# SHC_USB_HUB.net
KiCad netlist of a schematic drawn in EasyEDA
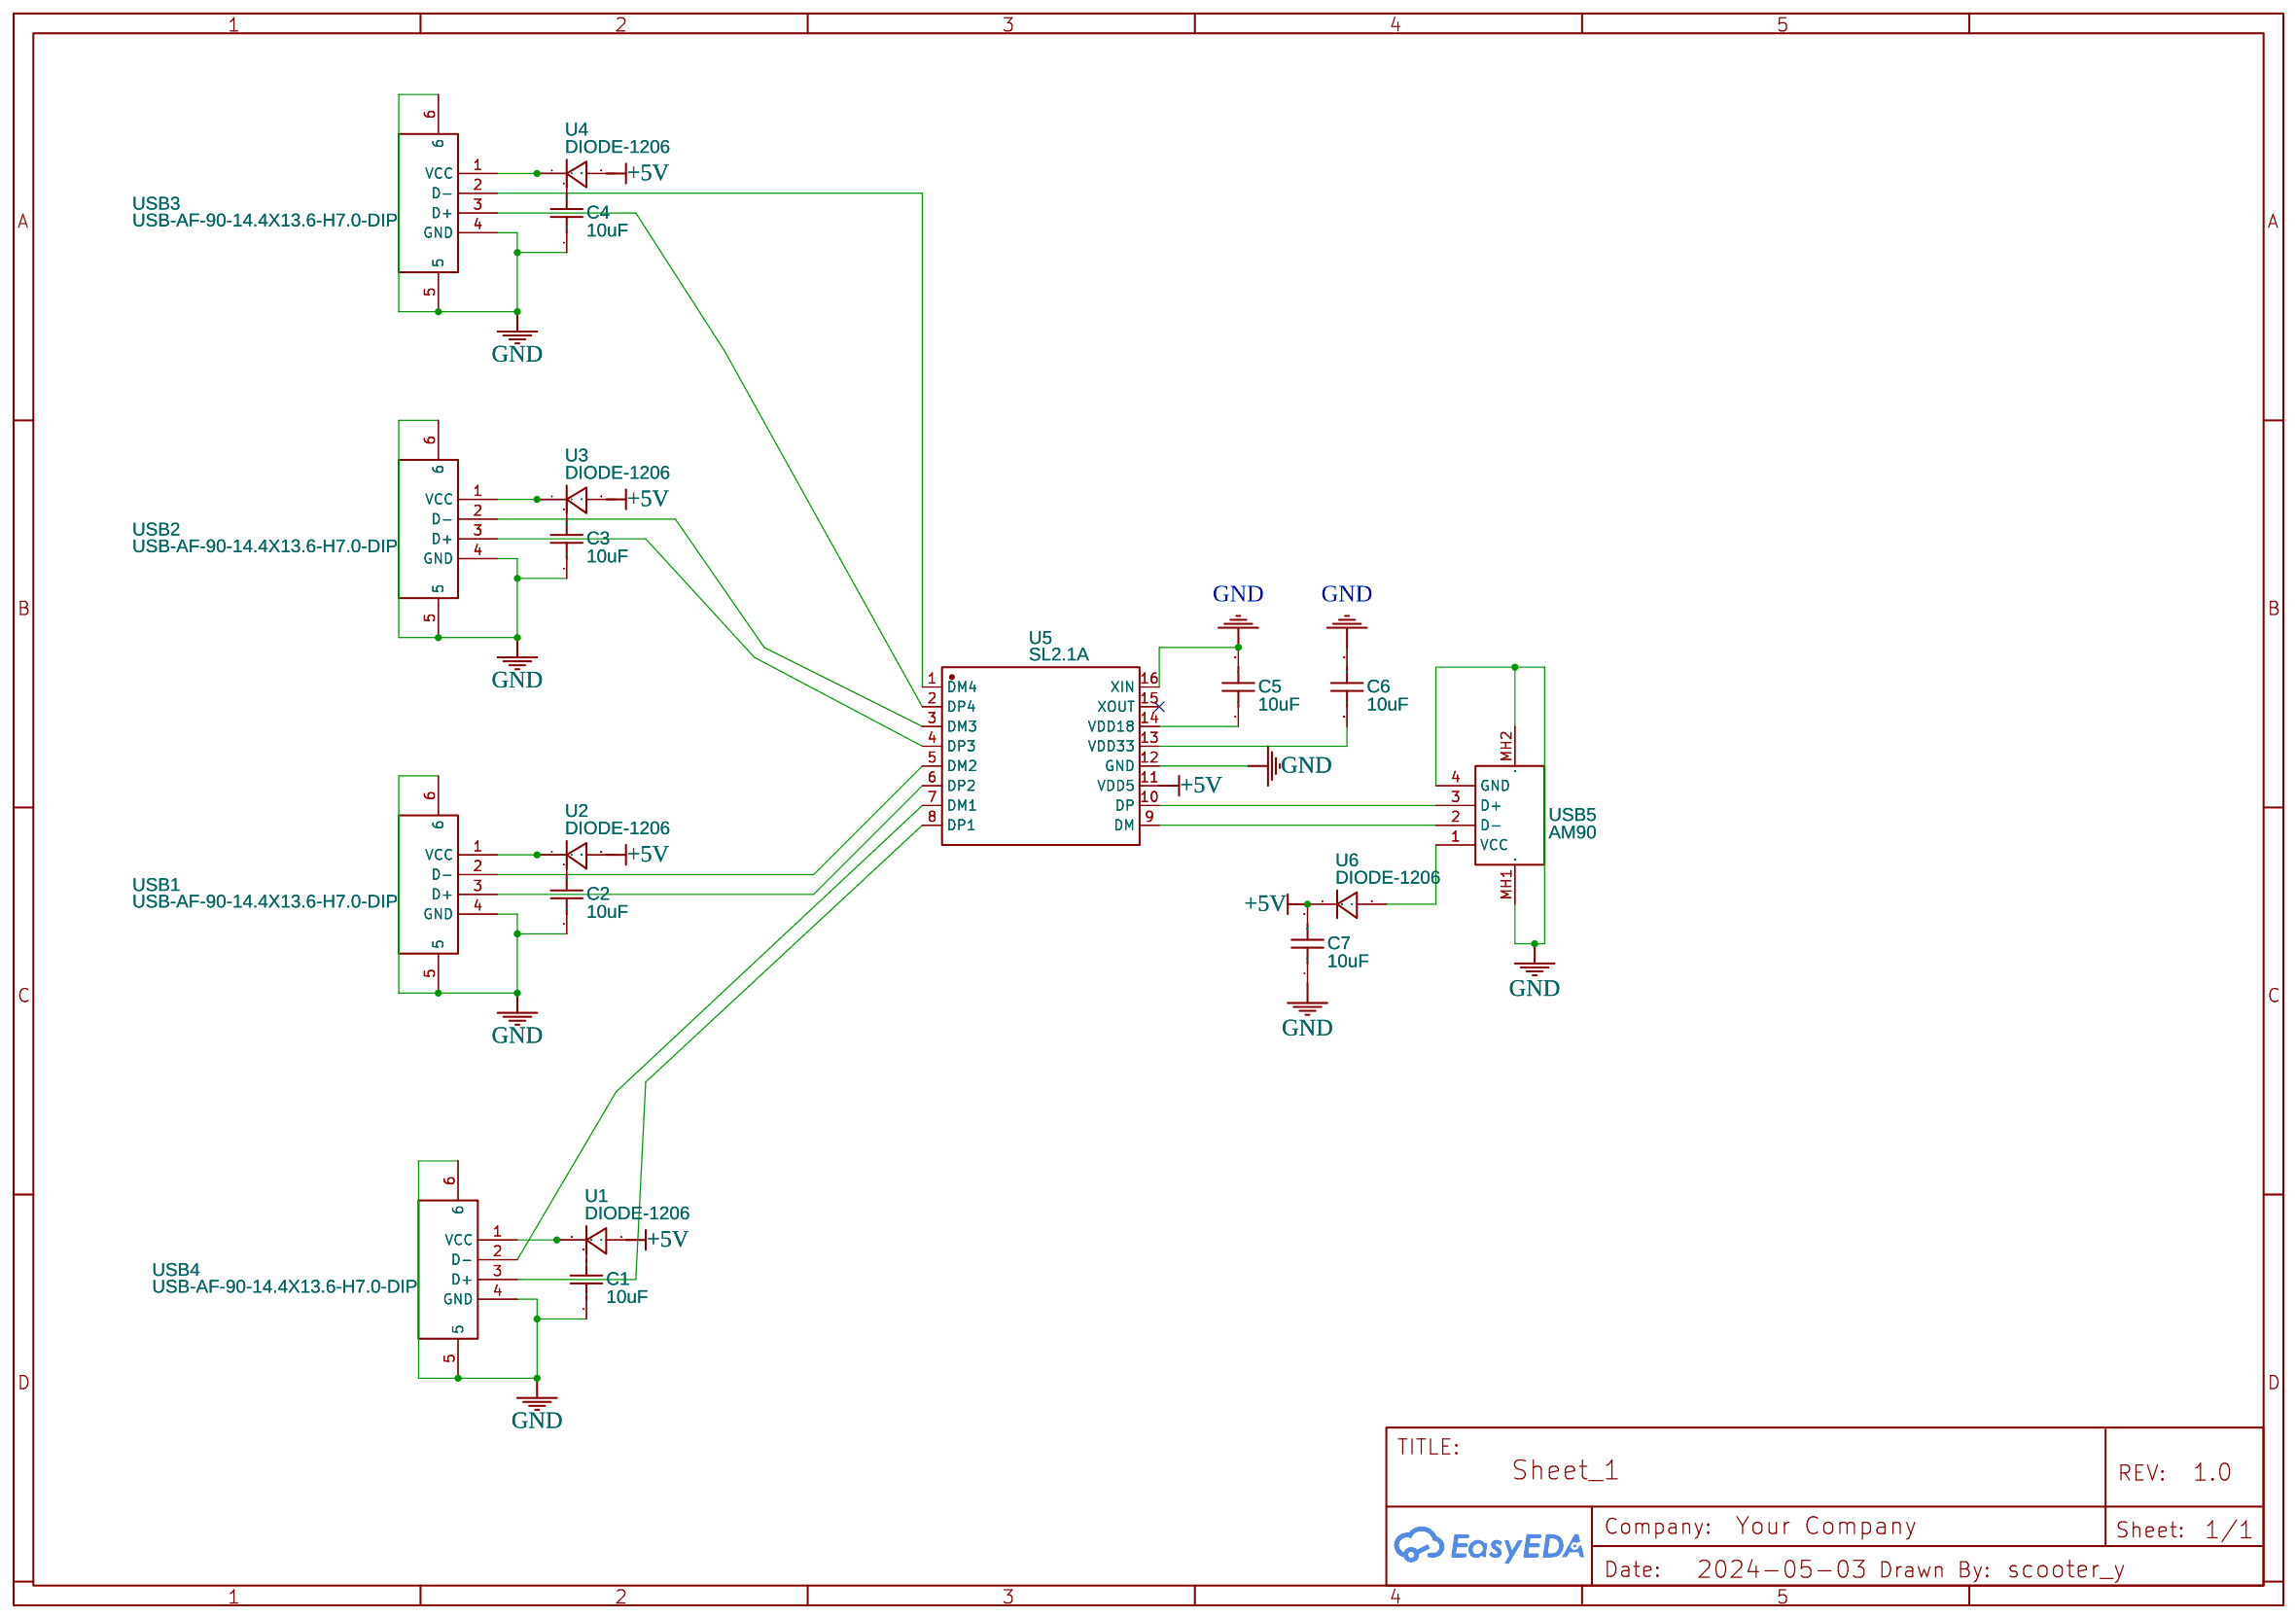
[diagram p0: schematic sheet]

(export (version "E")
  (design (tool "Eeschema 10.0.6"))
  (components
    (comp (ref "C1")
      (value "10uF")
      (fields (field (name "Manufacturer") "SAMSUNG(三星)"))
      (libsource (lib "") (part "10UF"))
    )
    (comp (ref "C2")
      (value "10uF")
      (fields (field (name "Manufacturer") "SAMSUNG(三星)"))
      (libsource (lib "") (part "10UF"))
    )
    (comp (ref "C3")
      (value "10uF")
      (fields (field (name "Manufacturer") "SAMSUNG(三星)"))
      (libsource (lib "") (part "10UF"))
    )
    (comp (ref "C4")
      (value "10uF")
      (fields (field (name "Manufacturer") "SAMSUNG(三星)"))
      (libsource (lib "") (part "10UF"))
    )
    (comp (ref "C5")
      (value "10uF")
      (fields (field (name "Manufacturer") "SAMSUNG(三星)"))
      (libsource (lib "") (part "10UF"))
    )
    (comp (ref "C6")
      (value "10uF")
      (fields (field (name "Manufacturer") "SAMSUNG(三星)"))
      (libsource (lib "") (part "10UF"))
    )
    (comp (ref "C7")
      (value "10uF")
      (fields (field (name "Manufacturer") "SAMSUNG(三星)"))
      (libsource (lib "") (part "10UF"))
    )
    (comp (ref "U1") (value "DIODE-1206") (libsource (lib "") (part "DIODE-1206")))
    (comp (ref "U2") (value "DIODE-1206") (libsource (lib "") (part "DIODE-1206")))
    (comp (ref "U3") (value "DIODE-1206") (libsource (lib "") (part "DIODE-1206")))
    (comp (ref "U4") (value "DIODE-1206") (libsource (lib "") (part "DIODE-1206")))
    (comp (ref "U5")
      (value "SL2.1A")
      (fields (field (name "Manufacturer") "CoreChips(和芯润德)"))
      (libsource (lib "") (part "SL2.1A"))
    )
    (comp (ref "U6") (value "DIODE-1206") (libsource (lib "") (part "DIODE-1206")))
    (comp (ref "USB1")
      (value "USB-AF-90-14.4X13.6-H7.0-DIP")
      (fields (field (name "Manufacturer Part") "903-131A1011D10100") (field (name "Manufacturer") "精拓金"))
      (libsource (lib "") (part "USB-AF-90-14.4X13.6-H7.0-DIP"))
    )
    (comp (ref "USB2")
      (value "USB-AF-90-14.4X13.6-H7.0-DIP")
      (fields (field (name "Manufacturer Part") "903-131A1011D10100") (field (name "Manufacturer") "精拓金"))
      (libsource (lib "") (part "USB-AF-90-14.4X13.6-H7.0-DIP"))
    )
    (comp (ref "USB3")
      (value "USB-AF-90-14.4X13.6-H7.0-DIP")
      (fields (field (name "Manufacturer Part") "903-131A1011D10100") (field (name "Manufacturer") "精拓金"))
      (libsource (lib "") (part "USB-AF-90-14.4X13.6-H7.0-DIP"))
    )
    (comp (ref "USB4")
      (value "USB-AF-90-14.4X13.6-H7.0-DIP")
      (fields (field (name "Manufacturer Part") "903-131A1011D10100") (field (name "Manufacturer") "精拓金"))
      (libsource (lib "") (part "USB-AF-90-14.4X13.6-H7.0-DIP"))
    )
    (comp (ref "USB5")
      (value "AM90")
      (fields (field (name "Manufacturer") "SHOU HAN(首韩)"))
      (libsource (lib "") (part "AM90"))
    )
  )
  (nets
    (net (code "1") (name "+5V") (class "Default")
      (node (ref "C7") (pin "2") (pinfunction "2_2") (pintype "unspecified"))
      (node (ref "U5") (pin "11") (pinfunction "VDD5_11") (pintype "unspecified"))
      (node (ref "U6") (pin "1") (pinfunction "1_1") (pintype "unspecified"))
    )
    (net (code "2") (name "GND") (class "Default")
      (node (ref "C1") (pin "1") (pinfunction "1_1") (pintype "unspecified"))
      (node (ref "C2") (pin "1") (pinfunction "1_1") (pintype "unspecified"))
      (node (ref "C3") (pin "1") (pinfunction "1_1") (pintype "unspecified"))
      (node (ref "C4") (pin "1") (pinfunction "1_1") (pintype "unspecified"))
      (node (ref "C5") (pin "2") (pinfunction "2_2") (pintype "unspecified"))
      (node (ref "C6") (pin "2") (pinfunction "2_2") (pintype "unspecified"))
      (node (ref "C7") (pin "1") (pinfunction "1_1") (pintype "unspecified"))
      (node (ref "U5") (pin "12") (pinfunction "GND_12") (pintype "unspecified"))
      (node (ref "U5") (pin "16") (pinfunction "XIN_16") (pintype "unspecified"))
      (node (ref "USB1") (pin "4") (pinfunction "GND_4") (pintype "unspecified"))
      (node (ref "USB1") (pin "5") (pinfunction "5_5") (pintype "unspecified"))
      (node (ref "USB1") (pin "6") (pinfunction "6_6") (pintype "unspecified"))
      (node (ref "USB2") (pin "4") (pinfunction "GND_4") (pintype "unspecified"))
      (node (ref "USB2") (pin "5") (pinfunction "5_5") (pintype "unspecified"))
      (node (ref "USB2") (pin "6") (pinfunction "6_6") (pintype "unspecified"))
      (node (ref "USB3") (pin "4") (pinfunction "GND_4") (pintype "unspecified"))
      (node (ref "USB3") (pin "5") (pinfunction "5_5") (pintype "unspecified"))
      (node (ref "USB3") (pin "6") (pinfunction "6_6") (pintype "unspecified"))
      (node (ref "USB4") (pin "4") (pinfunction "GND_4") (pintype "unspecified"))
      (node (ref "USB4") (pin "5") (pinfunction "5_5") (pintype "unspecified"))
      (node (ref "USB4") (pin "6") (pinfunction "6_6") (pintype "unspecified"))
      (node (ref "USB5") (pin "4") (pinfunction "GND_4") (pintype "input"))
      (node (ref "USB5") (pin "MH1") (pinfunction "MH1_MH1") (pintype "unspecified"))
      (node (ref "USB5") (pin "MH2") (pinfunction "MH2_MH2") (pintype "unspecified"))
    )
    (net (code "3") (name "Net-(U5-DM)") (class "Default")
      (node (ref "U5") (pin "9") (pinfunction "DM_9") (pintype "unspecified"))
      (node (ref "USB5") (pin "2") (pinfunction "D-_2") (pintype "input"))
    )
    (net (code "4") (name "Net-(U5-DM1)") (class "Default")
      (node (ref "U5") (pin "7") (pinfunction "DM1_7") (pintype "unspecified"))
      (node (ref "USB4") (pin "2") (pinfunction "D-_2") (pintype "unspecified"))
    )
    (net (code "5") (name "Net-(U5-DM2)") (class "Default")
      (node (ref "U5") (pin "5") (pinfunction "DM2_5") (pintype "unspecified"))
      (node (ref "USB1") (pin "2") (pinfunction "D-_2") (pintype "unspecified"))
    )
    (net (code "6") (name "Net-(U5-DM3)") (class "Default")
      (node (ref "U5") (pin "3") (pinfunction "DM3_3") (pintype "unspecified"))
      (node (ref "USB2") (pin "2") (pinfunction "D-_2") (pintype "unspecified"))
    )
    (net (code "7") (name "Net-(U5-DM4)") (class "Default")
      (node (ref "U5") (pin "1") (pinfunction "DM4_1") (pintype "unspecified"))
      (node (ref "USB3") (pin "2") (pinfunction "D-_2") (pintype "unspecified"))
    )
    (net (code "8") (name "Net-(U5-DP)") (class "Default")
      (node (ref "U5") (pin "10") (pinfunction "DP_10") (pintype "unspecified"))
      (node (ref "USB5") (pin "3") (pinfunction "D+_3") (pintype "input"))
    )
    (net (code "9") (name "Net-(U5-DP1)") (class "Default")
      (node (ref "U5") (pin "8") (pinfunction "DP1_8") (pintype "unspecified"))
      (node (ref "USB4") (pin "3") (pinfunction "D+_3") (pintype "unspecified"))
    )
    (net (code "10") (name "Net-(U5-DP2)") (class "Default")
      (node (ref "U5") (pin "6") (pinfunction "DP2_6") (pintype "unspecified"))
      (node (ref "USB1") (pin "3") (pinfunction "D+_3") (pintype "unspecified"))
    )
    (net (code "11") (name "Net-(U5-DP3)") (class "Default")
      (node (ref "U5") (pin "4") (pinfunction "DP3_4") (pintype "unspecified"))
      (node (ref "USB2") (pin "3") (pinfunction "D+_3") (pintype "unspecified"))
    )
    (net (code "12") (name "Net-(U5-DP4)") (class "Default")
      (node (ref "U5") (pin "2") (pinfunction "DP4_2") (pintype "unspecified"))
      (node (ref "USB3") (pin "3") (pinfunction "D+_3") (pintype "unspecified"))
    )
    (net (code "13") (name "Net-(U5-VDD18)") (class "Default")
      (node (ref "C5") (pin "1") (pinfunction "1_1") (pintype "unspecified"))
      (node (ref "U5") (pin "14") (pinfunction "VDD18_14") (pintype "unspecified"))
    )
    (net (code "14") (name "Net-(U5-VDD33)") (class "Default")
      (node (ref "C6") (pin "1") (pinfunction "1_1") (pintype "unspecified"))
      (node (ref "U5") (pin "13") (pinfunction "VDD33_13") (pintype "unspecified"))
    )
    (net (code "15") (name "Net-(USB1-VCC)") (class "Default")
      (node (ref "C2") (pin "2") (pinfunction "2_2") (pintype "unspecified"))
      (node (ref "U2") (pin "1") (pinfunction "1_1") (pintype "unspecified"))
      (node (ref "USB1") (pin "1") (pinfunction "VCC_1") (pintype "unspecified"))
    )
    (net (code "16") (name "Net-(USB2-VCC)") (class "Default")
      (node (ref "C3") (pin "2") (pinfunction "2_2") (pintype "unspecified"))
      (node (ref "U3") (pin "1") (pinfunction "1_1") (pintype "unspecified"))
      (node (ref "USB2") (pin "1") (pinfunction "VCC_1") (pintype "unspecified"))
    )
    (net (code "17") (name "Net-(USB3-VCC)") (class "Default")
      (node (ref "C4") (pin "2") (pinfunction "2_2") (pintype "unspecified"))
      (node (ref "U4") (pin "1") (pinfunction "1_1") (pintype "unspecified"))
      (node (ref "USB3") (pin "1") (pinfunction "VCC_1") (pintype "unspecified"))
    )
    (net (code "18") (name "Net-(USB4-VCC)") (class "Default")
      (node (ref "C1") (pin "2") (pinfunction "2_2") (pintype "unspecified"))
      (node (ref "U1") (pin "1") (pinfunction "1_1") (pintype "unspecified"))
      (node (ref "USB4") (pin "1") (pinfunction "VCC_1") (pintype "unspecified"))
    )
    (net (code "19") (name "Net-(USB5-VCC)") (class "Default")
      (node (ref "U6") (pin "2") (pinfunction "2_2") (pintype "unspecified"))
      (node (ref "USB5") (pin "1") (pinfunction "VCC_1") (pintype "input"))
    )
    (net (code "20") (name "unconnected-(U1-Pad2)") (class "Default")
      (node (ref "U1") (pin "2") (pinfunction "2_2") (pintype "unspecified"))
    )
    (net (code "21") (name "unconnected-(U2-Pad2)") (class "Default")
      (node (ref "U2") (pin "2") (pinfunction "2_2") (pintype "unspecified"))
    )
    (net (code "22") (name "unconnected-(U3-Pad2)") (class "Default")
      (node (ref "U3") (pin "2") (pinfunction "2_2") (pintype "unspecified"))
    )
    (net (code "23") (name "unconnected-(U4-Pad2)") (class "Default")
      (node (ref "U4") (pin "2") (pinfunction "2_2") (pintype "unspecified"))
    )
    (net (code "24") (name "unconnected-(U5-XOUT-Pad15)") (class "Default")
      (node (ref "U5") (pin "15") (pinfunction "XOUT_15") (pintype "unspecified+no_connect"))
    )
  )
)
